# ARE_adaptadora_AT90-8515_40pin.net
KiCad netlist of a schematic drawn in EAGLE
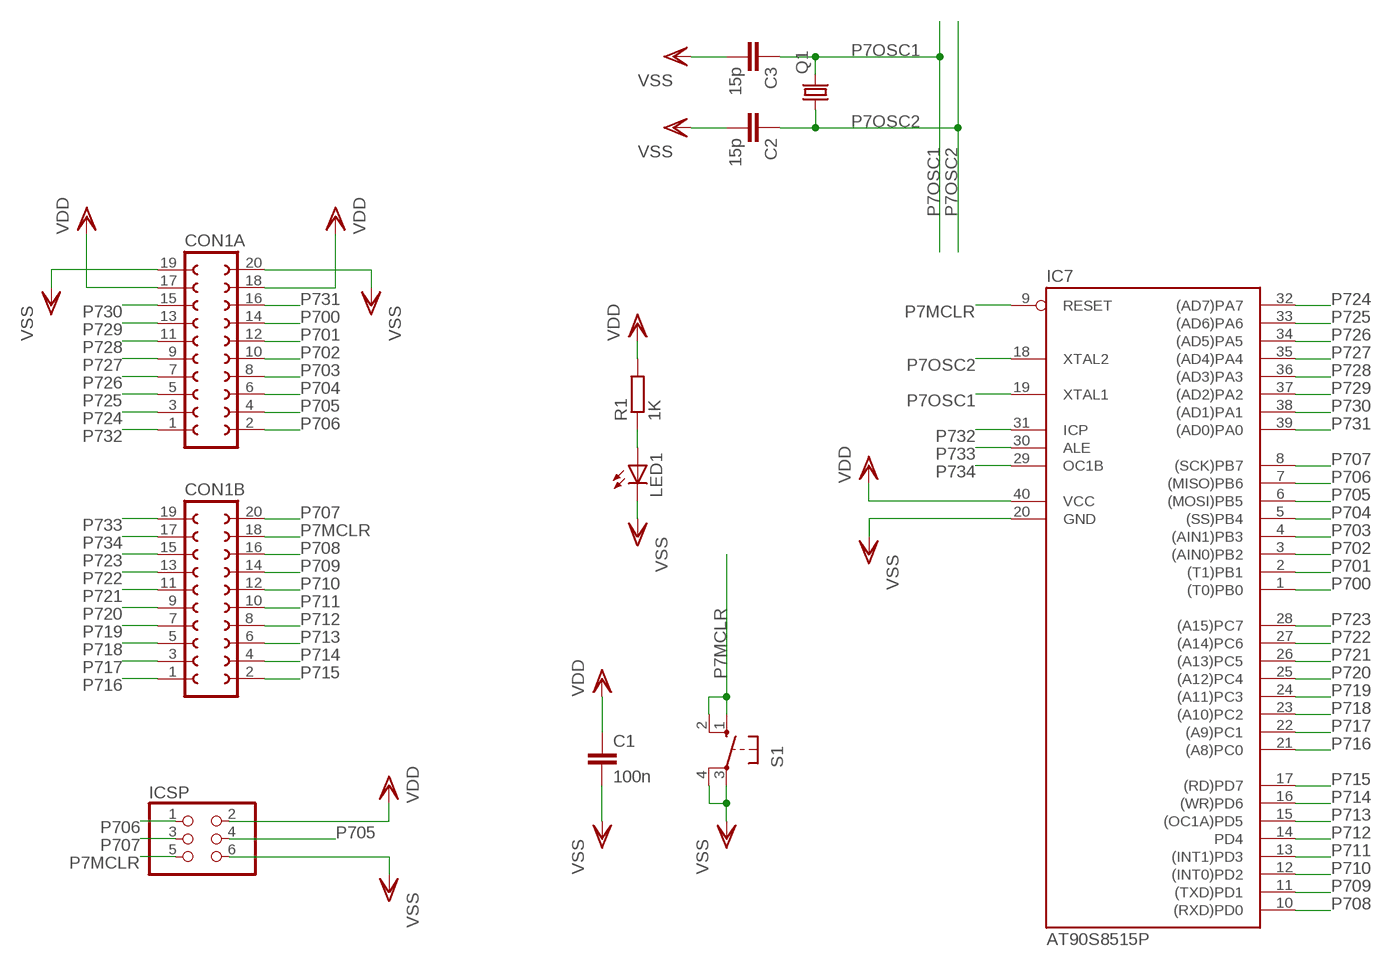
[diagram p0: schematic, sheet 1]

(export (version "E")
  (design (tool "Eeschema 10.0.6"))
  (components
    (comp (ref "C1")
      (value "100n")
      (footprint "eagle-import:C0805")
      (libsource (lib "eagle-import") (part "C-EUC0805"))
    )
    (comp (ref "C2")
      (value "15p")
      (footprint "eagle-import:C0805")
      (libsource (lib "eagle-import") (part "C-EUC0805"))
    )
    (comp (ref "C3")
      (value "15p")
      (footprint "eagle-import:C0805")
      (libsource (lib "eagle-import") (part "C-EUC0805"))
    )
    (comp (ref "CON1A")
      (value "FE10-2W")
      (footprint "eagle-import:FE10-2W")
      (libsource (lib "eagle-import") (part "FE10-2W"))
    )
    (comp (ref "CON1B")
      (value "FE10-2W")
      (footprint "eagle-import:FE10-2W")
      (libsource (lib "eagle-import") (part "FE10-2W"))
    )
    (comp (ref "IC7")
      (value "AT90S8515P")
      (footprint "eagle-import:DIL40")
      (libsource (lib "eagle-import") (part "AT90S8515P"))
    )
    (comp (ref "ICSP")
      (value "PINHD-2X3")
      (footprint "eagle-import:2X03")
      (libsource (lib "eagle-import") (part "PINHD-2X3"))
    )
    (comp (ref "LED1")
      (value "LED3MM")
      (footprint "eagle-import:LED3MM")
      (libsource (lib "eagle-import") (part "LED3MM"))
    )
    (comp (ref "Q1")
      (value "CRYSTALHC18U-V")
      (footprint "eagle-import:HC18U-V")
      (libsource (lib "eagle-import") (part "CRYSTALHC18U-V"))
    )
    (comp (ref "R1")
      (value "1K")
      (footprint "eagle-import:R0805")
      (libsource (lib "eagle-import") (part "R-EU_R0805"))
    )
    (comp (ref "S1")
      (value "10-XX")
      (footprint "eagle-import:B3F-10XX")
      (fields
        (field (name "MPN") "B3F-1000")
        (field (name "MPN_1") "B3F-1000")
        (field (name "OC_FARNELL") "176432")
        (field (name "OC_NEWARK") "36M3542")
      )
      (libsource (lib "eagle-import") (part "10-XX"))
    )
  )
  (nets
    (net (code "1") (name "/P7MCLR") (class "Default")
      (node (ref "CON1B") (pin "18") (pinfunction "18_18") (pintype "passive"))
      (node (ref "IC7") (pin "9") (pinfunction "RESET_9") (pintype "input"))
      (node (ref "ICSP") (pin "5") (pinfunction "5_5") (pintype "passive"))
      (node (ref "S1") (pin "1") (pinfunction "S_1") (pintype "passive"))
      (node (ref "S1") (pin "2") (pinfunction "S1_2") (pintype "passive"))
    )
    (net (code "2") (name "/P7OSC1") (class "Default")
      (node (ref "C3") (pin "1") (pinfunction "1_1") (pintype "passive"))
      (node (ref "IC7") (pin "19") (pinfunction "XTAL1_19") (pintype "bidirectional"))
      (node (ref "Q1") (pin "2") (pinfunction "2_2") (pintype "passive"))
    )
    (net (code "3") (name "/P7OSC2") (class "Default")
      (node (ref "C2") (pin "1") (pinfunction "1_1") (pintype "passive"))
      (node (ref "IC7") (pin "18") (pinfunction "XTAL2_18") (pintype "bidirectional"))
      (node (ref "Q1") (pin "1") (pinfunction "1_1") (pintype "passive"))
    )
    (net (code "4") (name "/P700") (class "Default")
      (node (ref "CON1A") (pin "14") (pinfunction "14_14") (pintype "passive"))
      (node (ref "IC7") (pin "1") (pinfunction "(T0)PB0_1") (pintype "bidirectional"))
    )
    (net (code "5") (name "/P701") (class "Default")
      (node (ref "CON1A") (pin "12") (pinfunction "12_12") (pintype "passive"))
      (node (ref "IC7") (pin "2") (pinfunction "(T1)PB1_2") (pintype "bidirectional"))
    )
    (net (code "6") (name "/P702") (class "Default")
      (node (ref "CON1A") (pin "10") (pinfunction "10_10") (pintype "passive"))
      (node (ref "IC7") (pin "3") (pinfunction "(AIN0)PB2_3") (pintype "bidirectional"))
    )
    (net (code "7") (name "/P703") (class "Default")
      (node (ref "CON1A") (pin "8") (pinfunction "8_8") (pintype "passive"))
      (node (ref "IC7") (pin "4") (pinfunction "(AIN1)PB3_4") (pintype "bidirectional"))
    )
    (net (code "8") (name "/P704") (class "Default")
      (node (ref "CON1A") (pin "6") (pinfunction "6_6") (pintype "passive"))
      (node (ref "IC7") (pin "5") (pinfunction "(SS)PB4_5") (pintype "bidirectional"))
    )
    (net (code "9") (name "/P705") (class "Default")
      (node (ref "CON1A") (pin "4") (pinfunction "4_4") (pintype "passive"))
      (node (ref "IC7") (pin "6") (pinfunction "(MOSI)PB5_6") (pintype "bidirectional"))
      (node (ref "ICSP") (pin "4") (pinfunction "4_4") (pintype "passive"))
    )
    (net (code "10") (name "/P706") (class "Default")
      (node (ref "CON1A") (pin "2") (pinfunction "2_2") (pintype "passive"))
      (node (ref "IC7") (pin "7") (pinfunction "(MISO)PB6_7") (pintype "bidirectional"))
      (node (ref "ICSP") (pin "1") (pinfunction "1_1") (pintype "passive"))
    )
    (net (code "11") (name "/P707") (class "Default")
      (node (ref "CON1B") (pin "20") (pinfunction "20_20") (pintype "passive"))
      (node (ref "IC7") (pin "8") (pinfunction "(SCK)PB7_8") (pintype "bidirectional"))
      (node (ref "ICSP") (pin "3") (pinfunction "3_3") (pintype "passive"))
    )
    (net (code "12") (name "/P708") (class "Default")
      (node (ref "CON1B") (pin "16") (pinfunction "16_16") (pintype "passive"))
      (node (ref "IC7") (pin "10") (pinfunction "(RXD)PD0_10") (pintype "bidirectional"))
    )
    (net (code "13") (name "/P709") (class "Default")
      (node (ref "CON1B") (pin "14") (pinfunction "14_14") (pintype "passive"))
      (node (ref "IC7") (pin "11") (pinfunction "(TXD)PD1_11") (pintype "bidirectional"))
    )
    (net (code "14") (name "/P710") (class "Default")
      (node (ref "CON1B") (pin "12") (pinfunction "12_12") (pintype "passive"))
      (node (ref "IC7") (pin "12") (pinfunction "(INT0)PD2_12") (pintype "bidirectional"))
    )
    (net (code "15") (name "/P711") (class "Default")
      (node (ref "CON1B") (pin "10") (pinfunction "10_10") (pintype "passive"))
      (node (ref "IC7") (pin "13") (pinfunction "(INT1)PD3_13") (pintype "bidirectional"))
    )
    (net (code "16") (name "/P712") (class "Default")
      (node (ref "CON1B") (pin "8") (pinfunction "8_8") (pintype "passive"))
      (node (ref "IC7") (pin "14") (pinfunction "PD4_14") (pintype "bidirectional"))
    )
    (net (code "17") (name "/P713") (class "Default")
      (node (ref "CON1B") (pin "6") (pinfunction "6_6") (pintype "passive"))
      (node (ref "IC7") (pin "15") (pinfunction "(OC1A)PD5_15") (pintype "bidirectional"))
    )
    (net (code "18") (name "/P714") (class "Default")
      (node (ref "CON1B") (pin "4") (pinfunction "4_4") (pintype "passive"))
      (node (ref "IC7") (pin "16") (pinfunction "(WR)PD6_16") (pintype "bidirectional"))
    )
    (net (code "19") (name "/P715") (class "Default")
      (node (ref "CON1B") (pin "2") (pinfunction "2_2") (pintype "passive"))
      (node (ref "IC7") (pin "17") (pinfunction "(RD)PD7_17") (pintype "bidirectional"))
    )
    (net (code "20") (name "/P716") (class "Default")
      (node (ref "CON1B") (pin "1") (pinfunction "1_1") (pintype "passive"))
      (node (ref "IC7") (pin "21") (pinfunction "(A8)PC0_21") (pintype "bidirectional"))
    )
    (net (code "21") (name "/P717") (class "Default")
      (node (ref "CON1B") (pin "3") (pinfunction "3_3") (pintype "passive"))
      (node (ref "IC7") (pin "22") (pinfunction "(A9)PC1_22") (pintype "bidirectional"))
    )
    (net (code "22") (name "/P718") (class "Default")
      (node (ref "CON1B") (pin "5") (pinfunction "5_5") (pintype "passive"))
      (node (ref "IC7") (pin "23") (pinfunction "(A10)PC2_23") (pintype "bidirectional"))
    )
    (net (code "23") (name "/P719") (class "Default")
      (node (ref "CON1B") (pin "7") (pinfunction "7_7") (pintype "passive"))
      (node (ref "IC7") (pin "24") (pinfunction "(A11)PC3_24") (pintype "bidirectional"))
    )
    (net (code "24") (name "/P720") (class "Default")
      (node (ref "CON1B") (pin "9") (pinfunction "9_9") (pintype "passive"))
      (node (ref "IC7") (pin "25") (pinfunction "(A12)PC4_25") (pintype "bidirectional"))
    )
    (net (code "25") (name "/P721") (class "Default")
      (node (ref "CON1B") (pin "11") (pinfunction "11_11") (pintype "passive"))
      (node (ref "IC7") (pin "26") (pinfunction "(A13)PC5_26") (pintype "bidirectional"))
    )
    (net (code "26") (name "/P722") (class "Default")
      (node (ref "CON1B") (pin "13") (pinfunction "13_13") (pintype "passive"))
      (node (ref "IC7") (pin "27") (pinfunction "(A14)PC6_27") (pintype "bidirectional"))
    )
    (net (code "27") (name "/P723") (class "Default")
      (node (ref "CON1B") (pin "15") (pinfunction "15_15") (pintype "passive"))
      (node (ref "IC7") (pin "28") (pinfunction "(A15)PC7_28") (pintype "bidirectional"))
    )
    (net (code "28") (name "/P724") (class "Default")
      (node (ref "CON1A") (pin "3") (pinfunction "3_3") (pintype "passive"))
      (node (ref "IC7") (pin "32") (pinfunction "(AD7)PA7_32") (pintype "bidirectional"))
    )
    (net (code "29") (name "/P725") (class "Default")
      (node (ref "CON1A") (pin "5") (pinfunction "5_5") (pintype "passive"))
      (node (ref "IC7") (pin "33") (pinfunction "(AD6)PA6_33") (pintype "bidirectional"))
    )
    (net (code "30") (name "/P726") (class "Default")
      (node (ref "CON1A") (pin "7") (pinfunction "7_7") (pintype "passive"))
      (node (ref "IC7") (pin "34") (pinfunction "(AD5)PA5_34") (pintype "bidirectional"))
    )
    (net (code "31") (name "/P727") (class "Default")
      (node (ref "CON1A") (pin "9") (pinfunction "9_9") (pintype "passive"))
      (node (ref "IC7") (pin "35") (pinfunction "(AD4)PA4_35") (pintype "bidirectional"))
    )
    (net (code "32") (name "/P728") (class "Default")
      (node (ref "CON1A") (pin "11") (pinfunction "11_11") (pintype "passive"))
      (node (ref "IC7") (pin "36") (pinfunction "(AD3)PA3_36") (pintype "bidirectional"))
    )
    (net (code "33") (name "/P729") (class "Default")
      (node (ref "CON1A") (pin "13") (pinfunction "13_13") (pintype "passive"))
      (node (ref "IC7") (pin "37") (pinfunction "(AD2)PA2_37") (pintype "bidirectional"))
    )
    (net (code "34") (name "/P730") (class "Default")
      (node (ref "CON1A") (pin "15") (pinfunction "15_15") (pintype "passive"))
      (node (ref "IC7") (pin "38") (pinfunction "(AD1)PA1_38") (pintype "bidirectional"))
    )
    (net (code "35") (name "/P731") (class "Default")
      (node (ref "CON1A") (pin "16") (pinfunction "16_16") (pintype "passive"))
      (node (ref "IC7") (pin "39") (pinfunction "(AD0)PA0_39") (pintype "bidirectional"))
    )
    (net (code "36") (name "/P732") (class "Default")
      (node (ref "CON1A") (pin "1") (pinfunction "1_1") (pintype "passive"))
      (node (ref "IC7") (pin "31") (pinfunction "ICP_31") (pintype "bidirectional"))
    )
    (net (code "37") (name "/P733") (class "Default")
      (node (ref "CON1B") (pin "19") (pinfunction "19_19") (pintype "passive"))
      (node (ref "IC7") (pin "30") (pinfunction "ALE_30") (pintype "bidirectional"))
    )
    (net (code "38") (name "/P734") (class "Default")
      (node (ref "CON1B") (pin "17") (pinfunction "17_17") (pintype "passive"))
      (node (ref "IC7") (pin "29") (pinfunction "OC1B_29") (pintype "bidirectional"))
    )
    (net (code "39") (name "Net-(LED1-PadA)") (class "Default")
      (node (ref "LED1") (pin "A") (pinfunction "A_A") (pintype "passive"))
      (node (ref "R1") (pin "1") (pinfunction "1_1") (pintype "passive"))
    )
    (net (code "40") (name "VDD") (class "Default")
      (node (ref "C1") (pin "1") (pinfunction "1_1") (pintype "passive"))
      (node (ref "CON1A") (pin "17") (pinfunction "17_17") (pintype "passive"))
      (node (ref "CON1A") (pin "18") (pinfunction "18_18") (pintype "passive"))
      (node (ref "IC7") (pin "40") (pinfunction "VCC_40") (pintype "power_in"))
      (node (ref "ICSP") (pin "2") (pinfunction "2_2") (pintype "passive"))
      (node (ref "R1") (pin "2") (pinfunction "2_2") (pintype "passive"))
    )
    (net (code "41") (name "VSS") (class "Default")
      (node (ref "C1") (pin "2") (pinfunction "2_2") (pintype "passive"))
      (node (ref "C2") (pin "2") (pinfunction "2_2") (pintype "passive"))
      (node (ref "C3") (pin "2") (pinfunction "2_2") (pintype "passive"))
      (node (ref "CON1A") (pin "19") (pinfunction "19_19") (pintype "passive"))
      (node (ref "CON1A") (pin "20") (pinfunction "20_20") (pintype "passive"))
      (node (ref "IC7") (pin "20") (pinfunction "GND_20") (pintype "power_in"))
      (node (ref "ICSP") (pin "6") (pinfunction "6_6") (pintype "passive"))
      (node (ref "LED1") (pin "K") (pinfunction "C_K") (pintype "passive"))
      (node (ref "S1") (pin "3") (pinfunction "P_3") (pintype "passive"))
      (node (ref "S1") (pin "4") (pinfunction "P1_4") (pintype "passive"))
    )
  )
)
